# BRAIN.net
KiCad netlist of a schematic drawn in EAGLE
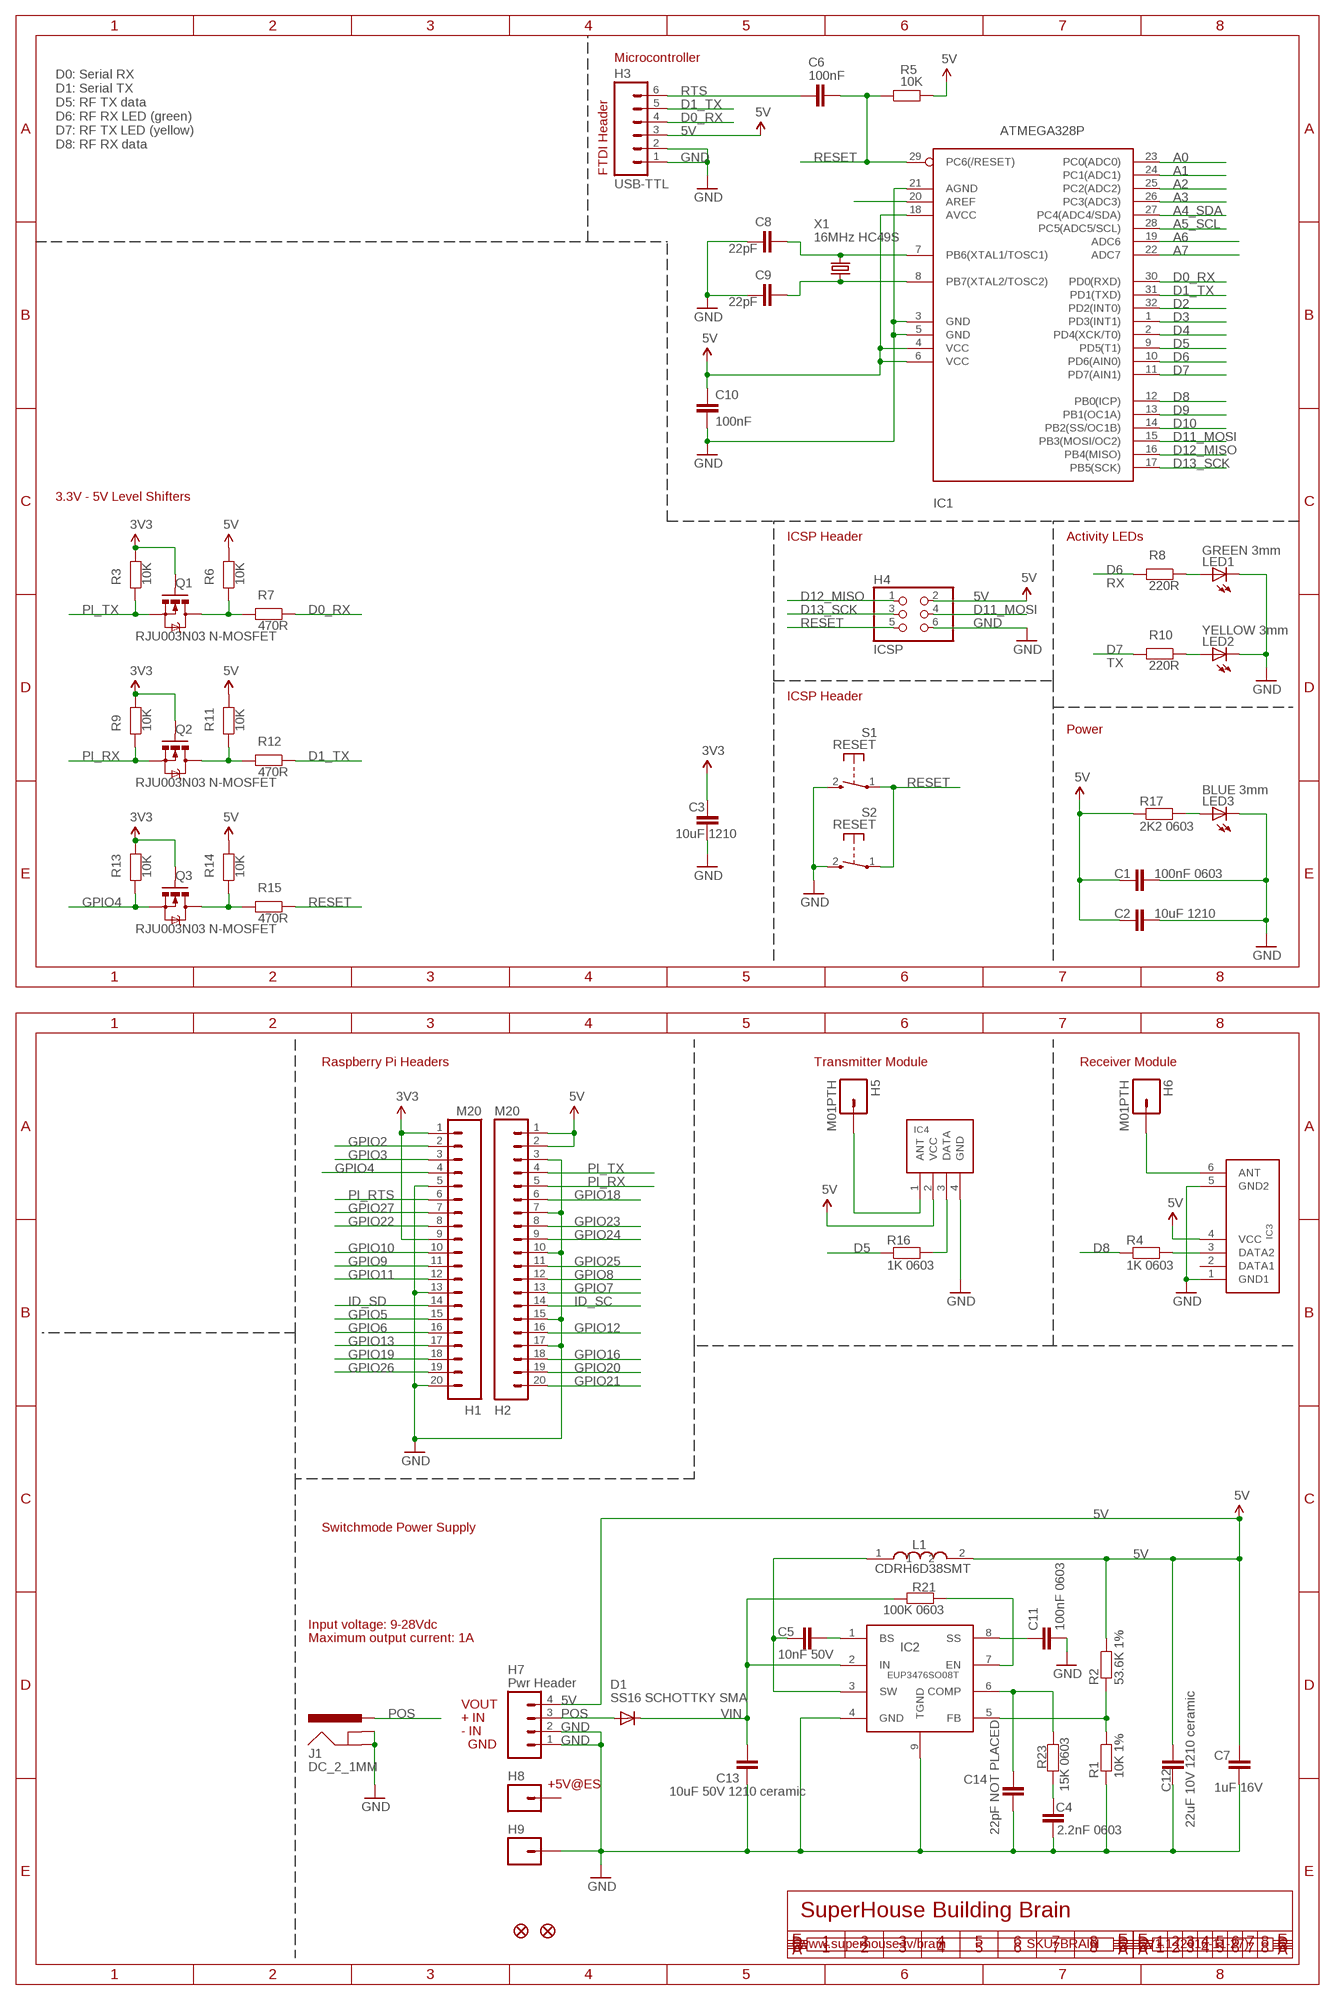
[diagram p0: schematic, sheet 1]

(export (version "E")
  (design (tool "Eeschema 10.0.6"))
  (components
    (comp (ref "C1")
      (value "100nF 0603")
      (footprint "eagle-import:0603")
      (libsource (lib "eagle-import") (part "CAP0603"))
    )
    (comp (ref "C2")
      (value "10uF 1210")
      (footprint "eagle-import:C1210")
      (libsource (lib "eagle-import") (part "C-EUC1210"))
    )
    (comp (ref "C3")
      (value "10uF 1210")
      (footprint "eagle-import:C1210")
      (libsource (lib "eagle-import") (part "C-EUC1210"))
    )
    (comp (ref "C4")
      (value "2.2nF 0603")
      (footprint "eagle-import:0603")
      (libsource (lib "eagle-import") (part "freetronics-marc_CAP0603"))
    )
    (comp (ref "C5")
      (value "10nF 50V")
      (footprint "eagle-import:0603")
      (libsource (lib "eagle-import") (part "freetronics-marc_CAP0603"))
    )
    (comp (ref "C6")
      (value "100nF")
      (footprint "eagle-import:0603")
      (libsource (lib "eagle-import") (part "freetronics-master-v1.1_CAP0603"))
    )
    (comp (ref "C7")
      (value "1uF 16V")
      (footprint "eagle-import:0603")
      (libsource (lib "eagle-import") (part "CAP0603"))
    )
    (comp (ref "C8")
      (value "22pF")
      (footprint "eagle-import:0603")
      (libsource (lib "eagle-import") (part "freetronics-master-v1.1_CAP0603"))
    )
    (comp (ref "C9")
      (value "22pF")
      (footprint "eagle-import:0603")
      (libsource (lib "eagle-import") (part "freetronics-master-v1.1_CAP0603"))
    )
    (comp (ref "C10")
      (value "100nF")
      (footprint "eagle-import:0603")
      (libsource (lib "eagle-import") (part "freetronics-master-v1.1_CAP0603"))
    )
    (comp (ref "C11")
      (value "100nF 0603")
      (footprint "eagle-import:0603")
      (libsource (lib "eagle-import") (part "freetronics-marc_CAP0603"))
    )
    (comp (ref "C12")
      (value "22uF 10V 1210 ceramic")
      (footprint "eagle-import:C1210")
      (libsource (lib "eagle-import") (part "C-EUC1210"))
    )
    (comp (ref "C13")
      (value "10uF 50V 1210 ceramic")
      (footprint "eagle-import:C1210")
      (libsource (lib "eagle-import") (part "C-EUC1210"))
    )
    (comp (ref "C14")
      (value "22pF NOT PLACED")
      (footprint "eagle-import:0603")
      (libsource (lib "eagle-import") (part "freetronics-marc_CAP0603"))
    )
    (comp (ref "D1")
      (value "SS16 SCHOTTKY SMA")
      (footprint "eagle-import:SMA-SMB-DIODE")
      (libsource (lib "eagle-import") (part "DIODESMAB"))
    )
    (comp (ref "H1")
      (value "M20")
      (footprint "eagle-import:1X20")
      (libsource (lib "eagle-import") (part "M20"))
    )
    (comp (ref "H2")
      (value "M20")
      (footprint "eagle-import:1X20")
      (libsource (lib "eagle-import") (part "M20"))
    )
    (comp (ref "H3")
      (value "USB-TTL")
      (footprint "eagle-import:1X06")
      (libsource (lib "eagle-import") (part "M06SIP"))
    )
    (comp (ref "H4")
      (value "ICSP")
      (footprint "eagle-import:2X03")
      (libsource (lib "eagle-import") (part "PINHD-2X3"))
    )
    (comp (ref "H5")
      (value "M01PTH")
      (footprint "eagle-import:1X01")
      (libsource (lib "eagle-import") (part "M01PTH"))
    )
    (comp (ref "H6")
      (value "M01PTH")
      (footprint "eagle-import:1X01")
      (libsource (lib "eagle-import") (part "M01PTH"))
    )
    (comp (ref "H7")
      (value "Pwr Header")
      (footprint "eagle-import:1X04")
      (libsource (lib "eagle-import") (part "M04PTH"))
    )
    (comp (ref "H8")
      (value "M01PTH")
      (footprint "eagle-import:1X01")
      (libsource (lib "eagle-import") (part "M01PTH"))
    )
    (comp (ref "H9")
      (value "M01PTH")
      (footprint "eagle-import:1X01")
      (libsource (lib "eagle-import") (part "M01PTH"))
    )
    (comp (ref "IC1")
      (value "ATMEGA328P")
      (footprint "eagle-import:TQFP32-08")
      (libsource (lib "eagle-import") (part "AVR-MEGA8-AI"))
    )
    (comp (ref "IC2")
      (value "EUP3476SO08T")
      (footprint "eagle-import:SO08T")
      (libsource (lib "eagle-import") (part "EUP3476SO08T"))
    )
    (comp (ref "IC3")
      (value "RXB1")
      (footprint "eagle-import:RX-B1-SHORT-FLAT")
      (libsource (lib "eagle-import") (part "RXB1SHORTFLAT"))
    )
    (comp (ref "IC4")
      (value "TX-C1FLAT")
      (footprint "eagle-import:TX-C1-FLAT")
      (libsource (lib "eagle-import") (part "TX-C1FLAT"))
    )
    (comp (ref "J1")
      (value "DC_2_1MM")
      (footprint "eagle-import:POWER_JACK_PTH")
      (libsource (lib "eagle-import") (part "POWER_JACKPTH"))
    )
    (comp (ref "L1")
      (value "CDRH6D38SMT")
      (footprint "eagle-import:CDRH")
      (libsource (lib "eagle-import") (part "CDRH6D38SMT"))
    )
    (comp (ref "LED1")
      (value "GREEN 3mm")
      (footprint "eagle-import:LED3MM")
      (libsource (lib "eagle-import") (part "LED3MM"))
    )
    (comp (ref "LED2")
      (value "YELLOW 3mm")
      (footprint "eagle-import:LED3MM")
      (libsource (lib "eagle-import") (part "LED3MM"))
    )
    (comp (ref "LED3")
      (value "BLUE 3mm")
      (footprint "eagle-import:LED3MM")
      (libsource (lib "eagle-import") (part "LED3MM"))
    )
    (comp (ref "Q1")
      (value "RJU003N03 N-MOSFET")
      (footprint "eagle-import:SOT32-3")
      (libsource (lib "eagle-import") (part "MOSFET-NSOT-323"))
    )
    (comp (ref "Q2")
      (value "RJU003N03 N-MOSFET")
      (footprint "eagle-import:SOT32-3")
      (libsource (lib "eagle-import") (part "MOSFET-NSOT-323"))
    )
    (comp (ref "Q3")
      (value "RJU003N03 N-MOSFET")
      (footprint "eagle-import:SOT32-3")
      (libsource (lib "eagle-import") (part "MOSFET-NSOT-323"))
    )
    (comp (ref "R1")
      (value "10K 1%")
      (footprint "eagle-import:0603")
      (libsource (lib "eagle-import") (part "RESISTOR0603"))
    )
    (comp (ref "R2")
      (value "53.6K 1%")
      (footprint "eagle-import:0603")
      (libsource (lib "eagle-import") (part "RESISTOR0603"))
    )
    (comp (ref "R3")
      (value "10K")
      (footprint "eagle-import:0603")
      (libsource (lib "eagle-import") (part "freetronics-master-v1.1_RESISTOR0603"))
    )
    (comp (ref "R4")
      (value "1K 0603")
      (footprint "eagle-import:0603")
      (libsource (lib "eagle-import") (part "RESISTOR0603"))
    )
    (comp (ref "R5")
      (value "10K")
      (footprint "eagle-import:0603")
      (libsource (lib "eagle-import") (part "freetronics-master-v1.1_RESISTOR0603"))
    )
    (comp (ref "R6")
      (value "10K")
      (footprint "eagle-import:0603")
      (libsource (lib "eagle-import") (part "freetronics-master-v1.1_RESISTOR0603"))
    )
    (comp (ref "R7")
      (value "470R")
      (footprint "eagle-import:0603")
      (libsource (lib "eagle-import") (part "freetronics-master-v1.1_RESISTOR0603"))
    )
    (comp (ref "R8")
      (value "220R")
      (footprint "eagle-import:0603")
      (libsource (lib "eagle-import") (part "freetronics-master-v1.1_RESISTOR0603"))
    )
    (comp (ref "R9")
      (value "10K")
      (footprint "eagle-import:0603")
      (libsource (lib "eagle-import") (part "freetronics-master-v1.1_RESISTOR0603"))
    )
    (comp (ref "R10")
      (value "220R")
      (footprint "eagle-import:0603")
      (libsource (lib "eagle-import") (part "freetronics-master-v1.1_RESISTOR0603"))
    )
    (comp (ref "R11")
      (value "10K")
      (footprint "eagle-import:0603")
      (libsource (lib "eagle-import") (part "freetronics-master-v1.1_RESISTOR0603"))
    )
    (comp (ref "R12")
      (value "470R")
      (footprint "eagle-import:0603")
      (libsource (lib "eagle-import") (part "freetronics-master-v1.1_RESISTOR0603"))
    )
    (comp (ref "R13")
      (value "10K")
      (footprint "eagle-import:0603")
      (libsource (lib "eagle-import") (part "freetronics-master-v1.1_RESISTOR0603"))
    )
    (comp (ref "R14")
      (value "10K")
      (footprint "eagle-import:0603")
      (libsource (lib "eagle-import") (part "freetronics-master-v1.1_RESISTOR0603"))
    )
    (comp (ref "R15")
      (value "470R")
      (footprint "eagle-import:0603")
      (libsource (lib "eagle-import") (part "freetronics-master-v1.1_RESISTOR0603"))
    )
    (comp (ref "R16")
      (value "1K 0603")
      (footprint "eagle-import:0603")
      (libsource (lib "eagle-import") (part "RESISTOR0603"))
    )
    (comp (ref "R17")
      (value "2K2 0603")
      (footprint "eagle-import:0603")
      (libsource (lib "eagle-import") (part "RESISTOR0603"))
    )
    (comp (ref "R21")
      (value "100K 0603")
      (footprint "eagle-import:0603")
      (libsource (lib "eagle-import") (part "freetronics-marc_RESISTOR0603"))
    )
    (comp (ref "R23")
      (value "15K 0603")
      (footprint "eagle-import:0603")
      (libsource (lib "eagle-import") (part "freetronics-marc_RESISTOR0603"))
    )
    (comp (ref "S1")
      (value "RESET")
      (footprint "eagle-import:TACTILE_SWITCH_SMD_2PIN_TINY")
      (libsource (lib "eagle-import") (part "TAC_SWITCH_2PIN"))
    )
    (comp (ref "S2")
      (value "RESET")
      (footprint "eagle-import:TACTILE_SWITCH_SMD_2PIN_TINY")
      (libsource (lib "eagle-import") (part "TAC_SWITCH_2PIN"))
    )
    (comp (ref "U$4")
      (value "FIDUCIAL1X2.5")
      (footprint "eagle-import:FIDUCIAL-1X2.5")
      (libsource (lib "eagle-import") (part "FIDUCIAL1X2.5"))
    )
    (comp (ref "U$5")
      (value "FIDUCIAL1X2.5")
      (footprint "eagle-import:FIDUCIAL-1X2.5")
      (libsource (lib "eagle-import") (part "FIDUCIAL1X2.5"))
    )
    (comp (ref "X1")
      (value "16MHz HC49S")
      (footprint "eagle-import:HC49U-V")
      (libsource (lib "eagle-import") (part "CRYSTALHC49UV"))
    )
  )
  (nets
    (net (code "1") (name "/A0") (class "Default")
      (node (ref "IC1") (pin "23") (pinfunction "PC0(ADC0)_23") (pintype "bidirectional"))
    )
    (net (code "2") (name "/A1") (class "Default")
      (node (ref "IC1") (pin "24") (pinfunction "PC1(ADC1)_24") (pintype "bidirectional"))
    )
    (net (code "3") (name "/A2") (class "Default")
      (node (ref "IC1") (pin "25") (pinfunction "PC2(ADC2)_25") (pintype "bidirectional"))
    )
    (net (code "4") (name "/A3") (class "Default")
      (node (ref "IC1") (pin "26") (pinfunction "PC3(ADC3)_26") (pintype "bidirectional"))
    )
    (net (code "5") (name "/A4_SDA") (class "Default")
      (node (ref "IC1") (pin "27") (pinfunction "PC4(ADC4/SDA)_27") (pintype "bidirectional"))
    )
    (net (code "6") (name "/A5_SCL") (class "Default")
      (node (ref "IC1") (pin "28") (pinfunction "PC5(ADC5/SCL)_28") (pintype "bidirectional"))
    )
    (net (code "7") (name "/A6") (class "Default")
      (node (ref "IC1") (pin "19") (pinfunction "ADC6_19") (pintype "bidirectional"))
    )
    (net (code "8") (name "/A7") (class "Default")
      (node (ref "IC1") (pin "22") (pinfunction "ADC7_22") (pintype "bidirectional"))
    )
    (net (code "9") (name "/D0_RX") (class "Default")
      (node (ref "H3") (pin "4") (pinfunction "4_4") (pintype "passive"))
      (node (ref "IC1") (pin "30") (pinfunction "PD0(RXD)_30") (pintype "bidirectional"))
      (node (ref "R7") (pin "1") (pinfunction "1_1") (pintype "passive"))
    )
    (net (code "10") (name "/D1_TX") (class "Default")
      (node (ref "H3") (pin "5") (pinfunction "5_5") (pintype "passive"))
      (node (ref "IC1") (pin "31") (pinfunction "PD1(TXD)_31") (pintype "bidirectional"))
      (node (ref "R12") (pin "1") (pinfunction "1_1") (pintype "passive"))
    )
    (net (code "11") (name "/D2") (class "Default")
      (node (ref "IC1") (pin "32") (pinfunction "PD2(INT0)_32") (pintype "bidirectional"))
    )
    (net (code "12") (name "/D3") (class "Default")
      (node (ref "IC1") (pin "1") (pinfunction "PD3(INT1)_1") (pintype "bidirectional"))
    )
    (net (code "13") (name "/D4") (class "Default")
      (node (ref "IC1") (pin "2") (pinfunction "PD4(XCK/T0)_2") (pintype "bidirectional"))
    )
    (net (code "14") (name "/D5") (class "Default")
      (node (ref "IC1") (pin "9") (pinfunction "PD5(T1)_9") (pintype "bidirectional"))
      (node (ref "R16") (pin "1") (pinfunction "1_1") (pintype "passive"))
    )
    (net (code "15") (name "/D6") (class "Default")
      (node (ref "IC1") (pin "10") (pinfunction "PD6(AIN0)_10") (pintype "bidirectional"))
      (node (ref "R8") (pin "2") (pinfunction "2_2") (pintype "passive"))
    )
    (net (code "16") (name "/D7") (class "Default")
      (node (ref "IC1") (pin "11") (pinfunction "PD7(AIN1)_11") (pintype "bidirectional"))
      (node (ref "R10") (pin "2") (pinfunction "2_2") (pintype "passive"))
    )
    (net (code "17") (name "/D8") (class "Default")
      (node (ref "IC1") (pin "12") (pinfunction "PB0(ICP)_12") (pintype "bidirectional"))
      (node (ref "R4") (pin "1") (pinfunction "1_1") (pintype "passive"))
    )
    (net (code "18") (name "/D9") (class "Default")
      (node (ref "IC1") (pin "13") (pinfunction "PB1(OC1A)_13") (pintype "bidirectional"))
    )
    (net (code "19") (name "/D10") (class "Default")
      (node (ref "IC1") (pin "14") (pinfunction "PB2(SS/OC1B)_14") (pintype "bidirectional"))
    )
    (net (code "20") (name "/D11_MOSI") (class "Default")
      (node (ref "H4") (pin "4") (pinfunction "4_4") (pintype "passive"))
      (node (ref "IC1") (pin "15") (pinfunction "PB3(MOSI/OC2)_15") (pintype "bidirectional"))
    )
    (net (code "21") (name "/D12_MISO") (class "Default")
      (node (ref "H4") (pin "1") (pinfunction "1_1") (pintype "passive"))
      (node (ref "IC1") (pin "16") (pinfunction "PB4(MISO)_16") (pintype "bidirectional"))
    )
    (net (code "22") (name "/D13_SCK") (class "Default")
      (node (ref "H4") (pin "3") (pinfunction "3_3") (pintype "passive"))
      (node (ref "IC1") (pin "17") (pinfunction "PB5(SCK)_17") (pintype "bidirectional"))
    )
    (net (code "23") (name "/GPIO2") (class "Default")
      (node (ref "H1") (pin "2") (pinfunction "2_2") (pintype "passive"))
    )
    (net (code "24") (name "/GPIO3") (class "Default")
      (node (ref "H1") (pin "3") (pinfunction "3_3") (pintype "passive"))
    )
    (net (code "25") (name "/GPIO4") (class "Default")
      (node (ref "H1") (pin "4") (pinfunction "4_4") (pintype "passive"))
      (node (ref "Q3") (pin "2") (pinfunction "S_2") (pintype "passive"))
      (node (ref "R13") (pin "2") (pinfunction "2_2") (pintype "passive"))
    )
    (net (code "26") (name "/GPIO5") (class "Default")
      (node (ref "H1") (pin "15") (pinfunction "15_15") (pintype "passive"))
    )
    (net (code "27") (name "/GPIO6") (class "Default")
      (node (ref "H1") (pin "16") (pinfunction "16_16") (pintype "passive"))
    )
    (net (code "28") (name "/GPIO7") (class "Default")
      (node (ref "H2") (pin "13") (pinfunction "13_13") (pintype "passive"))
    )
    (net (code "29") (name "/GPIO8") (class "Default")
      (node (ref "H2") (pin "12") (pinfunction "12_12") (pintype "passive"))
    )
    (net (code "30") (name "/GPIO9") (class "Default")
      (node (ref "H1") (pin "11") (pinfunction "11_11") (pintype "passive"))
    )
    (net (code "31") (name "/GPIO10") (class "Default")
      (node (ref "H1") (pin "10") (pinfunction "10_10") (pintype "passive"))
    )
    (net (code "32") (name "/GPIO11") (class "Default")
      (node (ref "H1") (pin "12") (pinfunction "12_12") (pintype "passive"))
    )
    (net (code "33") (name "/GPIO12") (class "Default")
      (node (ref "H2") (pin "16") (pinfunction "16_16") (pintype "passive"))
    )
    (net (code "34") (name "/GPIO13") (class "Default")
      (node (ref "H1") (pin "17") (pinfunction "17_17") (pintype "passive"))
    )
    (net (code "35") (name "/GPIO16") (class "Default")
      (node (ref "H2") (pin "18") (pinfunction "18_18") (pintype "passive"))
    )
    (net (code "36") (name "/GPIO18") (class "Default")
      (node (ref "H2") (pin "6") (pinfunction "6_6") (pintype "passive"))
    )
    (net (code "37") (name "/GPIO19") (class "Default")
      (node (ref "H1") (pin "18") (pinfunction "18_18") (pintype "passive"))
    )
    (net (code "38") (name "/GPIO20") (class "Default")
      (node (ref "H2") (pin "19") (pinfunction "19_19") (pintype "passive"))
    )
    (net (code "39") (name "/GPIO21") (class "Default")
      (node (ref "H2") (pin "20") (pinfunction "20_20") (pintype "passive"))
    )
    (net (code "40") (name "/GPIO22") (class "Default")
      (node (ref "H1") (pin "8") (pinfunction "8_8") (pintype "passive"))
    )
    (net (code "41") (name "/GPIO23") (class "Default")
      (node (ref "H2") (pin "8") (pinfunction "8_8") (pintype "passive"))
    )
    (net (code "42") (name "/GPIO24") (class "Default")
      (node (ref "H2") (pin "9") (pinfunction "9_9") (pintype "passive"))
    )
    (net (code "43") (name "/GPIO25") (class "Default")
      (node (ref "H2") (pin "11") (pinfunction "11_11") (pintype "passive"))
    )
    (net (code "44") (name "/GPIO26") (class "Default")
      (node (ref "H1") (pin "19") (pinfunction "19_19") (pintype "passive"))
    )
    (net (code "45") (name "/GPIO27") (class "Default")
      (node (ref "H1") (pin "7") (pinfunction "7_7") (pintype "passive"))
    )
    (net (code "46") (name "/ID_SC") (class "Default")
      (node (ref "H2") (pin "14") (pinfunction "14_14") (pintype "passive"))
    )
    (net (code "47") (name "/ID_SD") (class "Default")
      (node (ref "H1") (pin "14") (pinfunction "14_14") (pintype "passive"))
    )
    (net (code "48") (name "/PI_RTS") (class "Default")
      (node (ref "H1") (pin "6") (pinfunction "6_6") (pintype "passive"))
    )
    (net (code "49") (name "/PI_RX") (class "Default")
      (node (ref "H2") (pin "5") (pinfunction "5_5") (pintype "passive"))
      (node (ref "Q2") (pin "2") (pinfunction "S_2") (pintype "passive"))
      (node (ref "R9") (pin "2") (pinfunction "2_2") (pintype "passive"))
    )
    (net (code "50") (name "/PI_TX") (class "Default")
      (node (ref "H2") (pin "4") (pinfunction "4_4") (pintype "passive"))
      (node (ref "Q1") (pin "2") (pinfunction "S_2") (pintype "passive"))
      (node (ref "R3") (pin "2") (pinfunction "2_2") (pintype "passive"))
    )
    (net (code "51") (name "/POS") (class "Default")
      (node (ref "D1") (pin "A") (pinfunction "A_A") (pintype "passive"))
      (node (ref "H7") (pin "3") (pinfunction "3_3") (pintype "passive"))
      (node (ref "J1") (pin "PWR") (pinfunction "PWR_PWR") (pintype "bidirectional"))
    )
    (net (code "52") (name "/RESET") (class "Default")
      (node (ref "C6") (pin "2") (pinfunction "2_2") (pintype "passive"))
      (node (ref "H4") (pin "5") (pinfunction "5_5") (pintype "passive"))
      (node (ref "IC1") (pin "29") (pinfunction "PC6(/RESET)_29") (pintype "bidirectional"))
      (node (ref "R15") (pin "1") (pinfunction "1_1") (pintype "passive"))
      (node (ref "R5") (pin "1") (pinfunction "1_1") (pintype "passive"))
      (node (ref "S1") (pin "1") (pinfunction "P_1") (pintype "passive"))
      (node (ref "S2") (pin "1") (pinfunction "P_1") (pintype "passive"))
    )
    (net (code "53") (name "/RTS") (class "Default")
      (node (ref "C6") (pin "1") (pinfunction "1_1") (pintype "passive"))
      (node (ref "H3") (pin "6") (pinfunction "6_6") (pintype "passive"))
    )
    (net (code "54") (name "/VIN") (class "Default")
      (node (ref "C13") (pin "1") (pinfunction "1_1") (pintype "passive"))
      (node (ref "D1") (pin "C") (pinfunction "C_C") (pintype "passive"))
      (node (ref "IC2") (pin "2") (pinfunction "IN_2") (pintype "power_in"))
      (node (ref "R21") (pin "2") (pinfunction "2_2") (pintype "passive"))
    )
    (net (code "55") (name "3V3") (class "Default")
      (node (ref "C3") (pin "1") (pinfunction "1_1") (pintype "passive"))
      (node (ref "H1") (pin "1") (pinfunction "1_1") (pintype "passive"))
      (node (ref "H1") (pin "9") (pinfunction "9_9") (pintype "passive"))
      (node (ref "Q1") (pin "1") (pinfunction "G_1") (pintype "passive"))
      (node (ref "Q2") (pin "1") (pinfunction "G_1") (pintype "passive"))
      (node (ref "Q3") (pin "1") (pinfunction "G_1") (pintype "passive"))
      (node (ref "R13") (pin "1") (pinfunction "1_1") (pintype "passive"))
      (node (ref "R3") (pin "1") (pinfunction "1_1") (pintype "passive"))
      (node (ref "R9") (pin "1") (pinfunction "1_1") (pintype "passive"))
    )
    (net (code "56") (name "5V") (class "Default")
      (node (ref "C1") (pin "1") (pinfunction "1_1") (pintype "passive"))
      (node (ref "C10") (pin "1") (pinfunction "1_1") (pintype "passive"))
      (node (ref "C12") (pin "1") (pinfunction "1_1") (pintype "passive"))
      (node (ref "C2") (pin "2") (pinfunction "2_2") (pintype "passive"))
      (node (ref "C7") (pin "1") (pinfunction "1_1") (pintype "passive"))
      (node (ref "H2") (pin "1") (pinfunction "1_1") (pintype "passive"))
      (node (ref "H2") (pin "2") (pinfunction "2_2") (pintype "passive"))
      (node (ref "H3") (pin "3") (pinfunction "3_3") (pintype "passive"))
      (node (ref "H4") (pin "2") (pinfunction "2_2") (pintype "passive"))
      (node (ref "H7") (pin "4") (pinfunction "4_4") (pintype "passive"))
      (node (ref "IC1") (pin "18") (pinfunction "AVCC_18") (pintype "bidirectional"))
      (node (ref "IC1") (pin "4") (pinfunction "VCC_4") (pintype "bidirectional"))
      (node (ref "IC1") (pin "6") (pinfunction "VCC_6") (pintype "bidirectional"))
      (node (ref "IC3") (pin "4") (pinfunction "VCC_4") (pintype "bidirectional"))
      (node (ref "IC4") (pin "2") (pinfunction "VCC_2") (pintype "power_in"))
      (node (ref "L1") (pin "2") (pinfunction "2_2") (pintype "bidirectional"))
      (node (ref "R11") (pin "1") (pinfunction "1_1") (pintype "passive"))
      (node (ref "R14") (pin "1") (pinfunction "1_1") (pintype "passive"))
      (node (ref "R17") (pin "1") (pinfunction "1_1") (pintype "passive"))
      (node (ref "R2") (pin "2") (pinfunction "2_2") (pintype "passive"))
      (node (ref "R5") (pin "2") (pinfunction "2_2") (pintype "passive"))
      (node (ref "R6") (pin "1") (pinfunction "1_1") (pintype "passive"))
    )
    (net (code "57") (name "GND") (class "Default")
      (node (ref "C1") (pin "2") (pinfunction "2_2") (pintype "passive"))
      (node (ref "C10") (pin "2") (pinfunction "2_2") (pintype "passive"))
      (node (ref "C11") (pin "2") (pinfunction "2_2") (pintype "passive"))
      (node (ref "C12") (pin "2") (pinfunction "2_2") (pintype "passive"))
      (node (ref "C13") (pin "2") (pinfunction "2_2") (pintype "passive"))
      (node (ref "C14") (pin "2") (pinfunction "2_2") (pintype "passive"))
      (node (ref "C2") (pin "1") (pinfunction "1_1") (pintype "passive"))
      (node (ref "C3") (pin "2") (pinfunction "2_2") (pintype "passive"))
      (node (ref "C4") (pin "2") (pinfunction "2_2") (pintype "passive"))
      (node (ref "C7") (pin "2") (pinfunction "2_2") (pintype "passive"))
      (node (ref "C8") (pin "1") (pinfunction "1_1") (pintype "passive"))
      (node (ref "C9") (pin "1") (pinfunction "1_1") (pintype "passive"))
      (node (ref "H1") (pin "13") (pinfunction "13_13") (pintype "passive"))
      (node (ref "H1") (pin "20") (pinfunction "20_20") (pintype "passive"))
      (node (ref "H1") (pin "5") (pinfunction "5_5") (pintype "passive"))
      (node (ref "H2") (pin "10") (pinfunction "10_10") (pintype "passive"))
      (node (ref "H2") (pin "15") (pinfunction "15_15") (pintype "passive"))
      (node (ref "H2") (pin "17") (pinfunction "17_17") (pintype "passive"))
      (node (ref "H2") (pin "3") (pinfunction "3_3") (pintype "passive"))
      (node (ref "H2") (pin "7") (pinfunction "7_7") (pintype "passive"))
      (node (ref "H3") (pin "1") (pinfunction "1_1") (pintype "passive"))
      (node (ref "H3") (pin "2") (pinfunction "2_2") (pintype "passive"))
      (node (ref "H4") (pin "6") (pinfunction "6_6") (pintype "passive"))
      (node (ref "H7") (pin "1") (pinfunction "1_1") (pintype "passive"))
      (node (ref "H7") (pin "2") (pinfunction "2_2") (pintype "passive"))
      (node (ref "H9") (pin "1") (pinfunction "1_1") (pintype "passive"))
      (node (ref "IC1") (pin "21") (pinfunction "AGND_21") (pintype "bidirectional"))
      (node (ref "IC1") (pin "3") (pinfunction "GND_3") (pintype "bidirectional"))
      (node (ref "IC1") (pin "5") (pinfunction "GND_5") (pintype "bidirectional"))
      (node (ref "IC2") (pin "4") (pinfunction "GND_4") (pintype "power_in"))
      (node (ref "IC2") (pin "9") (pinfunction "TGND_9") (pintype "power_in"))
      (node (ref "IC3") (pin "1") (pinfunction "GND1_1") (pintype "bidirectional"))
      (node (ref "IC3") (pin "5") (pinfunction "GND2_5") (pintype "bidirectional"))
      (node (ref "IC4") (pin "4") (pinfunction "GND_4") (pintype "power_in"))
      (node (ref "J1") (pin "GND") (pinfunction "GND_GND") (pintype "bidirectional"))
      (node (ref "J1") (pin "GNDBREAK") (pinfunction "GNDBREAK_GNDBREAK") (pintype "bidirectional"))
      (node (ref "LED1") (pin "K") (pinfunction "C_K") (pintype "passive"))
      (node (ref "LED2") (pin "K") (pinfunction "C_K") (pintype "passive"))
      (node (ref "LED3") (pin "K") (pinfunction "C_K") (pintype "passive"))
      (node (ref "R1") (pin "1") (pinfunction "1_1") (pintype "passive"))
      (node (ref "S1") (pin "2") (pinfunction "S_2") (pintype "passive"))
      (node (ref "S2") (pin "2") (pinfunction "S_2") (pintype "passive"))
    )
    (net (code "58") (name "Net-(C4-Pad1)") (class "Default")
      (node (ref "C4") (pin "1") (pinfunction "1_1") (pintype "passive"))
      (node (ref "R23") (pin "1") (pinfunction "1_1") (pintype "passive"))
    )
    (net (code "59") (name "Net-(IC1-PB6(XTAL1{slash}TOSC1))") (class "Default")
      (node (ref "C8") (pin "2") (pinfunction "2_2") (pintype "passive"))
      (node (ref "IC1") (pin "7") (pinfunction "PB6(XTAL1/TOSC1)_7") (pintype "bidirectional"))
      (node (ref "X1") (pin "2") (pinfunction "2_2") (pintype "passive"))
    )
    (net (code "60") (name "Net-(IC1-PB7(XTAL2{slash}TOSC2))") (class "Default")
      (node (ref "C9") (pin "2") (pinfunction "2_2") (pintype "passive"))
      (node (ref "IC1") (pin "8") (pinfunction "PB7(XTAL2/TOSC2)_8") (pintype "bidirectional"))
      (node (ref "X1") (pin "1") (pinfunction "1_1") (pintype "passive"))
    )
    (net (code "61") (name "Net-(IC2-BS)") (class "Default")
      (node (ref "C5") (pin "2") (pinfunction "2_2") (pintype "passive"))
      (node (ref "IC2") (pin "1") (pinfunction "BS_1") (pintype "bidirectional"))
    )
    (net (code "62") (name "Net-(IC2-COMP)") (class "Default")
      (node (ref "C14") (pin "1") (pinfunction "1_1") (pintype "passive"))
      (node (ref "IC2") (pin "6") (pinfunction "COMP_6") (pintype "bidirectional"))
      (node (ref "R23") (pin "2") (pinfunction "2_2") (pintype "passive"))
    )
    (net (code "63") (name "Net-(IC2-EN)") (class "Default")
      (node (ref "IC2") (pin "7") (pinfunction "EN_7") (pintype "input"))
      (node (ref "R21") (pin "1") (pinfunction "1_1") (pintype "passive"))
    )
    (net (code "64") (name "Net-(IC2-FB)") (class "Default")
      (node (ref "IC2") (pin "5") (pinfunction "FB_5") (pintype "bidirectional"))
      (node (ref "R1") (pin "2") (pinfunction "2_2") (pintype "passive"))
      (node (ref "R2") (pin "1") (pinfunction "1_1") (pintype "passive"))
    )
    (net (code "65") (name "Net-(IC2-SS)") (class "Default")
      (node (ref "C11") (pin "1") (pinfunction "1_1") (pintype "passive"))
      (node (ref "IC2") (pin "8") (pinfunction "SS_8") (pintype "bidirectional"))
    )
    (net (code "66") (name "Net-(IC2-SW)") (class "Default")
      (node (ref "C5") (pin "1") (pinfunction "1_1") (pintype "passive"))
      (node (ref "IC2") (pin "3") (pinfunction "SW_3") (pintype "bidirectional"))
      (node (ref "L1") (pin "1") (pinfunction "1_1") (pintype "bidirectional"))
    )
    (net (code "67") (name "Net-(IC3-ANT)") (class "Default")
      (node (ref "H6") (pin "1") (pinfunction "1_1") (pintype "passive"))
      (node (ref "IC3") (pin "6") (pinfunction "ANT_6") (pintype "bidirectional"))
    )
    (net (code "68") (name "Net-(IC3-DATA2)") (class "Default")
      (node (ref "IC3") (pin "3") (pinfunction "DATA2_3") (pintype "bidirectional"))
      (node (ref "R4") (pin "2") (pinfunction "2_2") (pintype "passive"))
    )
    (net (code "69") (name "Net-(IC4-ANT)") (class "Default")
      (node (ref "H5") (pin "1") (pinfunction "1_1") (pintype "passive"))
      (node (ref "IC4") (pin "1") (pinfunction "ANT_1") (pintype "output"))
    )
    (net (code "70") (name "Net-(IC4-DATA)") (class "Default")
      (node (ref "IC4") (pin "3") (pinfunction "DATA_3") (pintype "input"))
      (node (ref "R16") (pin "2") (pinfunction "2_2") (pintype "passive"))
    )
    (net (code "71") (name "Net-(LED1-PadA)") (class "Default")
      (node (ref "LED1") (pin "A") (pinfunction "A_A") (pintype "passive"))
      (node (ref "R8") (pin "1") (pinfunction "1_1") (pintype "passive"))
    )
    (net (code "72") (name "Net-(LED2-PadA)") (class "Default")
      (node (ref "LED2") (pin "A") (pinfunction "A_A") (pintype "passive"))
      (node (ref "R10") (pin "1") (pinfunction "1_1") (pintype "passive"))
    )
    (net (code "73") (name "Net-(LED3-PadA)") (class "Default")
      (node (ref "LED3") (pin "A") (pinfunction "A_A") (pintype "passive"))
      (node (ref "R17") (pin "2") (pinfunction "2_2") (pintype "passive"))
    )
    (net (code "74") (name "Net-(Q1-D)") (class "Default")
      (node (ref "Q1") (pin "3") (pinfunction "D_3") (pintype "passive"))
      (node (ref "R6") (pin "2") (pinfunction "2_2") (pintype "passive"))
      (node (ref "R7") (pin "2") (pinfunction "2_2") (pintype "passive"))
    )
    (net (code "75") (name "Net-(Q2-D)") (class "Default")
      (node (ref "Q2") (pin "3") (pinfunction "D_3") (pintype "passive"))
      (node (ref "R11") (pin "2") (pinfunction "2_2") (pintype "passive"))
      (node (ref "R12") (pin "2") (pinfunction "2_2") (pintype "passive"))
    )
    (net (code "76") (name "Net-(Q3-D)") (class "Default")
      (node (ref "Q3") (pin "3") (pinfunction "D_3") (pintype "passive"))
      (node (ref "R14") (pin "2") (pinfunction "2_2") (pintype "passive"))
      (node (ref "R15") (pin "2") (pinfunction "2_2") (pintype "passive"))
    )
    (net (code "77") (name "unconnected-(H8-Pad1)") (class "Default")
      (node (ref "H8") (pin "1") (pinfunction "1_1") (pintype "passive"))
    )
    (net (code "78") (name "unconnected-(IC1-AREF-Pad20)") (class "Default")
      (node (ref "IC1") (pin "20") (pinfunction "AREF_20") (pintype "bidirectional"))
    )
    (net (code "79") (name "unconnected-(IC3-DATA1-Pad2)") (class "Default")
      (node (ref "IC3") (pin "2") (pinfunction "DATA1_2") (pintype "bidirectional"))
    )
  )
)
